# MintyCharger_Rev_A.net
KiCad netlist of a schematic drawn in EAGLE
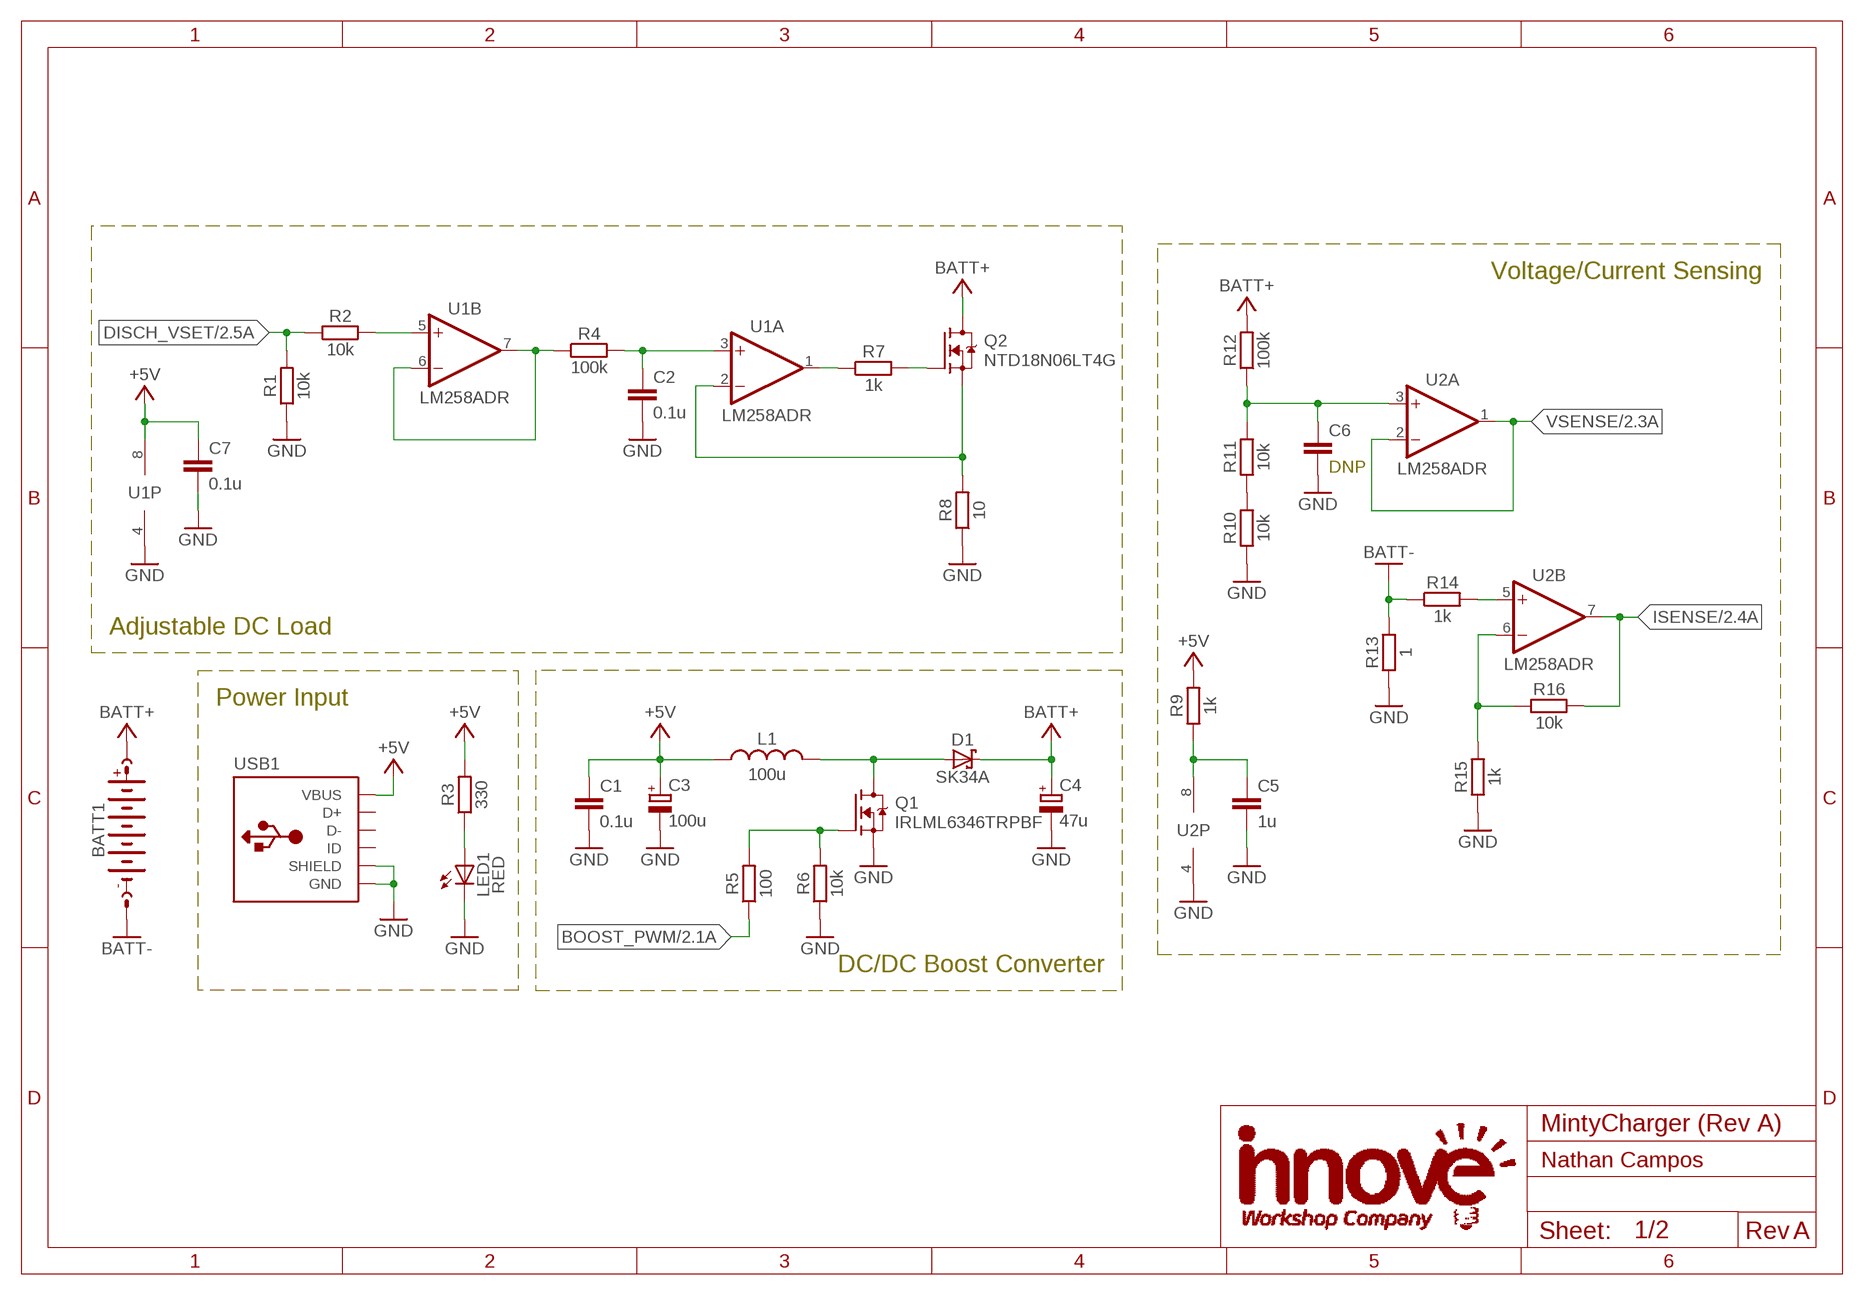
[diagram p0: schematic, sheet 1]
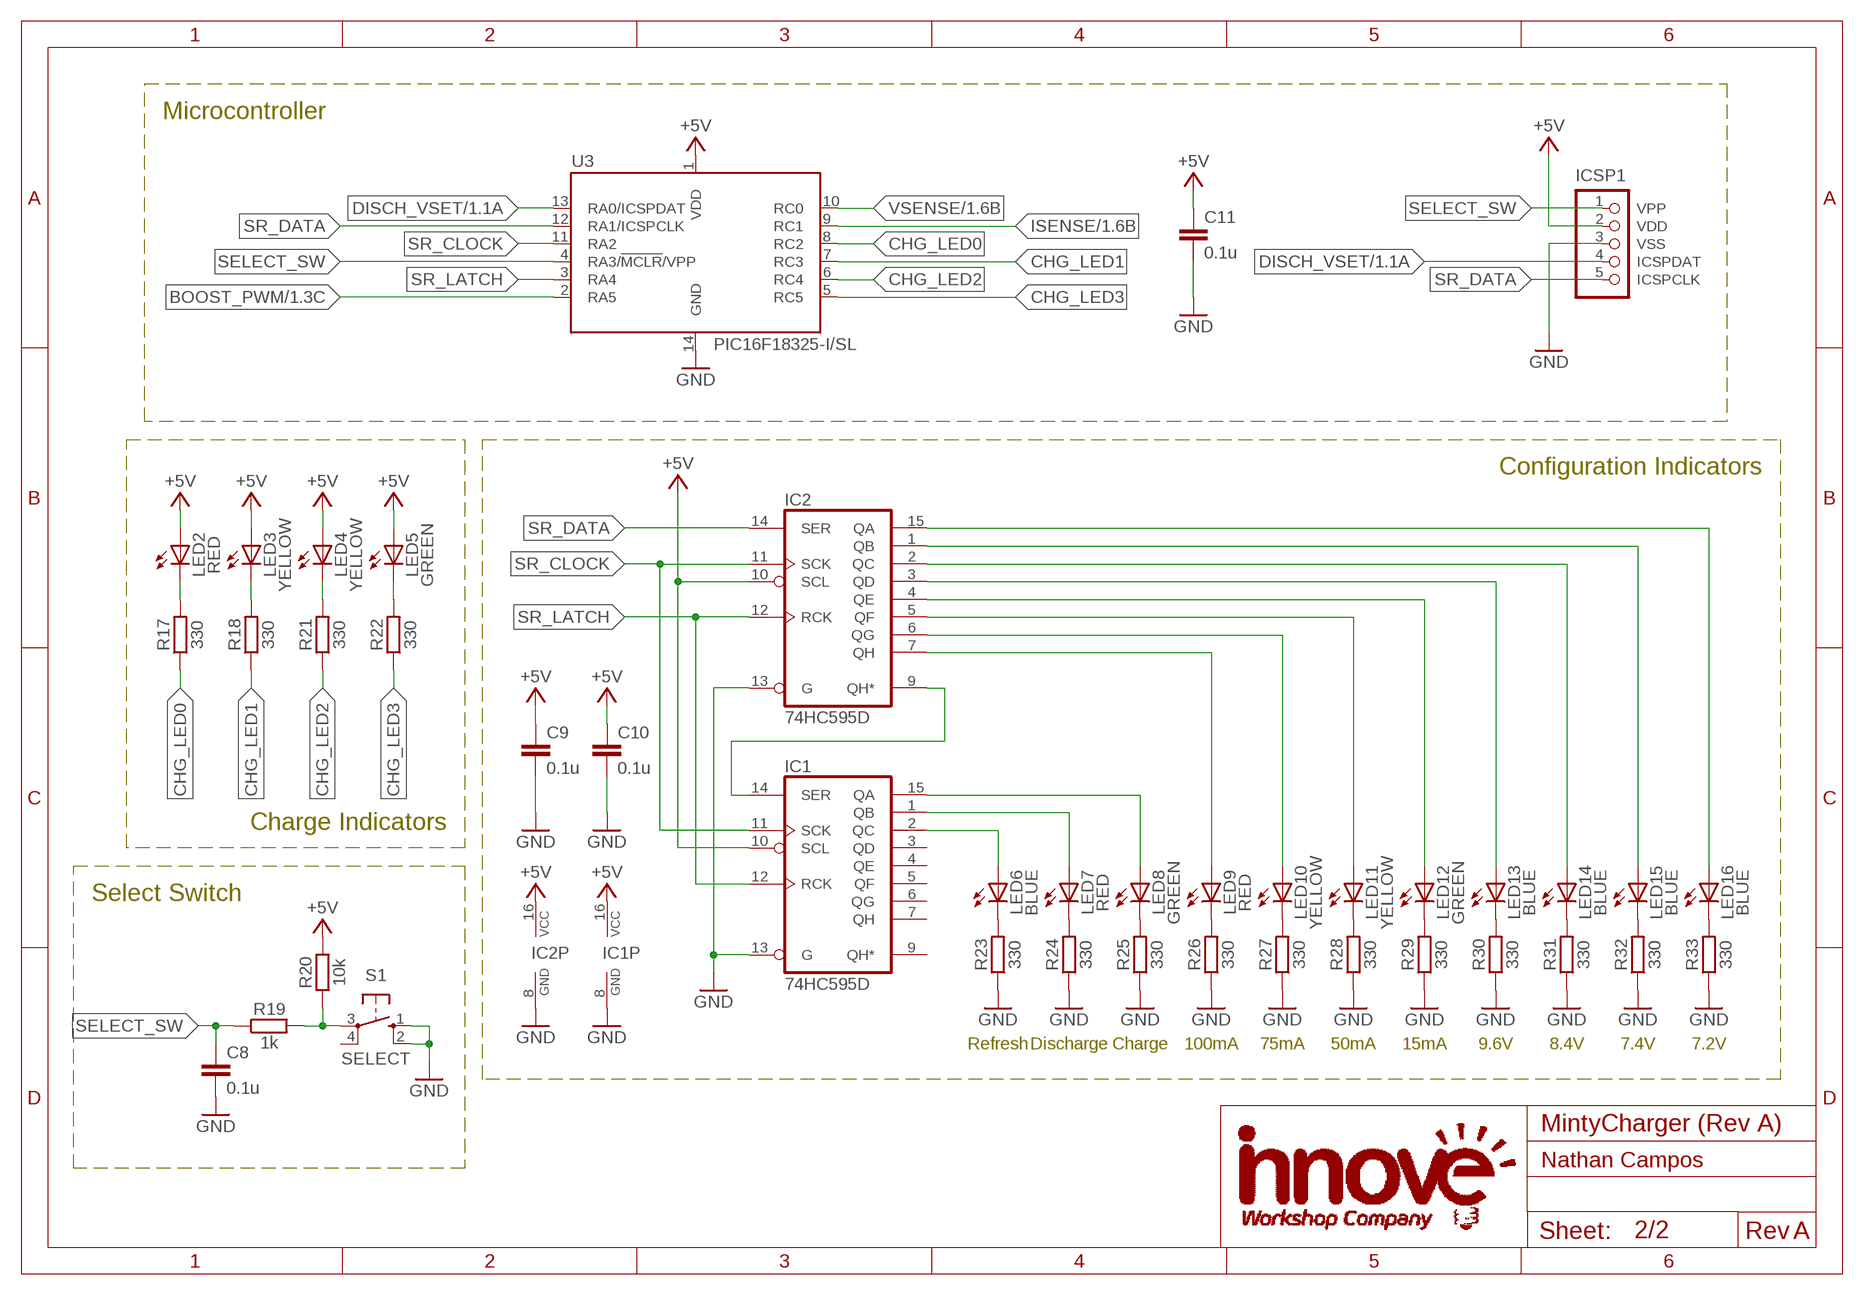
[diagram p1: schematic, sheet 2]

(export (version "E")
  (design (tool "Eeschema 10.0.6"))
  (components
    (comp (ref "C8")
      (value "0.1u")
      (footprint "eagle-import:C0805")
      (libsource (lib "eagle-import") (part "C0805"))
    )
    (comp (ref "C9")
      (value "0.1u")
      (footprint "eagle-import:C0805")
      (libsource (lib "eagle-import") (part "C0805"))
    )
    (comp (ref "C10")
      (value "0.1u")
      (footprint "eagle-import:C0805")
      (libsource (lib "eagle-import") (part "C0805"))
    )
    (comp (ref "C11")
      (value "0.1u")
      (footprint "eagle-import:C0805")
      (libsource (lib "eagle-import") (part "C0805"))
    )
    (comp (ref "IC1")
      (value "74HC595D")
      (footprint "eagle-import:SO16")
      (libsource (lib "eagle-import") (part "74595DHC"))
    )
    (comp (ref "IC2")
      (value "74HC595D")
      (footprint "eagle-import:SO16")
      (libsource (lib "eagle-import") (part "74595DHC"))
    )
    (comp (ref "ICSP1")
      (value "PIC-ICSPJST-XH")
      (footprint "eagle-import:B5B-XH-A")
      (libsource (lib "eagle-import") (part "PIC-ICSPJST-XH"))
    )
    (comp (ref "LED2")
      (value "RED")
      (footprint "eagle-import:CHIP-LED0805")
      (libsource (lib "eagle-import") (part "LEDCHIP-LED0805"))
    )
    (comp (ref "LED3")
      (value "YELLOW")
      (footprint "eagle-import:CHIP-LED0805")
      (libsource (lib "eagle-import") (part "LEDCHIP-LED0805"))
    )
    (comp (ref "LED4")
      (value "YELLOW")
      (footprint "eagle-import:CHIP-LED0805")
      (libsource (lib "eagle-import") (part "LEDCHIP-LED0805"))
    )
    (comp (ref "LED5")
      (value "GREEN")
      (footprint "eagle-import:CHIP-LED0805")
      (libsource (lib "eagle-import") (part "LEDCHIP-LED0805"))
    )
    (comp (ref "LED6")
      (value "BLUE")
      (footprint "eagle-import:CHIP-LED0805")
      (libsource (lib "eagle-import") (part "LEDCHIP-LED0805"))
    )
    (comp (ref "LED7")
      (value "RED")
      (footprint "eagle-import:CHIP-LED0805")
      (libsource (lib "eagle-import") (part "LEDCHIP-LED0805"))
    )
    (comp (ref "LED8")
      (value "GREEN")
      (footprint "eagle-import:CHIP-LED0805")
      (libsource (lib "eagle-import") (part "LEDCHIP-LED0805"))
    )
    (comp (ref "LED9")
      (value "RED")
      (footprint "eagle-import:CHIP-LED0805")
      (libsource (lib "eagle-import") (part "LEDCHIP-LED0805"))
    )
    (comp (ref "LED10")
      (value "YELLOW")
      (footprint "eagle-import:CHIP-LED0805")
      (libsource (lib "eagle-import") (part "LEDCHIP-LED0805"))
    )
    (comp (ref "LED11")
      (value "YELLOW")
      (footprint "eagle-import:CHIP-LED0805")
      (libsource (lib "eagle-import") (part "LEDCHIP-LED0805"))
    )
    (comp (ref "LED12")
      (value "GREEN")
      (footprint "eagle-import:CHIP-LED0805")
      (libsource (lib "eagle-import") (part "LEDCHIP-LED0805"))
    )
    (comp (ref "LED13")
      (value "BLUE")
      (footprint "eagle-import:CHIP-LED0805")
      (libsource (lib "eagle-import") (part "LEDCHIP-LED0805"))
    )
    (comp (ref "LED14")
      (value "BLUE")
      (footprint "eagle-import:CHIP-LED0805")
      (libsource (lib "eagle-import") (part "LEDCHIP-LED0805"))
    )
    (comp (ref "LED15")
      (value "BLUE")
      (footprint "eagle-import:CHIP-LED0805")
      (libsource (lib "eagle-import") (part "LEDCHIP-LED0805"))
    )
    (comp (ref "LED16")
      (value "BLUE")
      (footprint "eagle-import:CHIP-LED0805")
      (libsource (lib "eagle-import") (part "LEDCHIP-LED0805"))
    )
    (comp (ref "R17")
      (value "330")
      (footprint "eagle-import:R0805")
      (libsource (lib "eagle-import") (part "R0805"))
    )
    (comp (ref "R18")
      (value "330")
      (footprint "eagle-import:R0805")
      (libsource (lib "eagle-import") (part "R0805"))
    )
    (comp (ref "R19")
      (value "1k")
      (footprint "eagle-import:R0805")
      (libsource (lib "eagle-import") (part "R0805"))
    )
    (comp (ref "R20")
      (value "10k")
      (footprint "eagle-import:R0805")
      (libsource (lib "eagle-import") (part "R0805"))
    )
    (comp (ref "R21")
      (value "330")
      (footprint "eagle-import:R0805")
      (libsource (lib "eagle-import") (part "R0805"))
    )
    (comp (ref "R22")
      (value "330")
      (footprint "eagle-import:R0805")
      (libsource (lib "eagle-import") (part "R0805"))
    )
    (comp (ref "R23")
      (value "330")
      (footprint "eagle-import:R0805")
      (libsource (lib "eagle-import") (part "R0805"))
    )
    (comp (ref "R24")
      (value "330")
      (footprint "eagle-import:R0805")
      (libsource (lib "eagle-import") (part "R0805"))
    )
    (comp (ref "R25")
      (value "330")
      (footprint "eagle-import:R0805")
      (libsource (lib "eagle-import") (part "R0805"))
    )
    (comp (ref "R26")
      (value "330")
      (footprint "eagle-import:R0805")
      (libsource (lib "eagle-import") (part "R0805"))
    )
    (comp (ref "R27")
      (value "330")
      (footprint "eagle-import:R0805")
      (libsource (lib "eagle-import") (part "R0805"))
    )
    (comp (ref "R28")
      (value "330")
      (footprint "eagle-import:R0805")
      (libsource (lib "eagle-import") (part "R0805"))
    )
    (comp (ref "R29")
      (value "330")
      (footprint "eagle-import:R0805")
      (libsource (lib "eagle-import") (part "R0805"))
    )
    (comp (ref "R30")
      (value "330")
      (footprint "eagle-import:R0805")
      (libsource (lib "eagle-import") (part "R0805"))
    )
    (comp (ref "R31")
      (value "330")
      (footprint "eagle-import:R0805")
      (libsource (lib "eagle-import") (part "R0805"))
    )
    (comp (ref "R32")
      (value "330")
      (footprint "eagle-import:R0805")
      (libsource (lib "eagle-import") (part "R0805"))
    )
    (comp (ref "R33")
      (value "330")
      (footprint "eagle-import:R0805")
      (libsource (lib "eagle-import") (part "R0805"))
    )
    (comp (ref "S1")
      (value "SELECT")
      (footprint "eagle-import:PTS645-SMT")
      (libsource (lib "eagle-import") (part "TACT-4PIN-SMT"))
    )
    (comp (ref "U3")
      (value "PIC16F18325-I/SL")
      (footprint "eagle-import:SO14")
      (libsource (lib "eagle-import") (part "PIC16F18325-I/SL"))
    )
    (comp (ref "BATT1")
      (value "KEYSTONE-590-9V")
      (footprint "eagle-import:KEYSTONE-590-9V")
      (libsource (lib "eagle-import") (part "KEYSTONE-590-9V"))
    )
    (comp (ref "C1")
      (value "0.1u")
      (footprint "eagle-import:C0805")
      (libsource (lib "eagle-import") (part "C0805"))
    )
    (comp (ref "C2")
      (value "0.1u")
      (footprint "eagle-import:C0805")
      (libsource (lib "eagle-import") (part "C0805"))
    )
    (comp (ref "C3")
      (value "100u")
      (footprint "eagle-import:PANASONIC_D")
      (libsource (lib "eagle-import") (part "CPOL-MCVVT016M101EA1L"))
    )
    (comp (ref "C4")
      (value "47u")
      (footprint "eagle-import:PANASONIC_C")
      (libsource (lib "eagle-import") (part "CPOL-MCVVT016M470DA1L"))
    )
    (comp (ref "C5")
      (value "1u")
      (footprint "eagle-import:C0805")
      (libsource (lib "eagle-import") (part "C0805"))
    )
    (comp (ref "C6")
      (value "C0805")
      (footprint "eagle-import:C0805")
      (libsource (lib "eagle-import") (part "C0805"))
    )
    (comp (ref "C7")
      (value "0.1u")
      (footprint "eagle-import:C0805")
      (libsource (lib "eagle-import") (part "C0805"))
    )
    (comp (ref "D1")
      (value "SK34A")
      (footprint "eagle-import:SMA")
      (libsource (lib "eagle-import") (part "SK34A"))
    )
    (comp (ref "L1")
      (value "100u")
      (footprint "eagle-import:ELLCTP")
      (libsource (lib "eagle-import") (part "L-ELLCTP"))
    )
    (comp (ref "LED1")
      (value "RED")
      (footprint "eagle-import:CHIP-LED0805")
      (libsource (lib "eagle-import") (part "LEDCHIP-LED0805"))
    )
    (comp (ref "Q1")
      (value "IRLML6346TRPBF")
      (footprint "eagle-import:SOT23")
      (libsource (lib "eagle-import") (part "IRLML6346TRPBF"))
    )
    (comp (ref "Q2")
      (value "NTD18N06LT4G")
      (footprint "eagle-import:TO252")
      (libsource (lib "eagle-import") (part "NTD18N06LT4G"))
    )
    (comp (ref "R1")
      (value "10k")
      (footprint "eagle-import:R0805")
      (libsource (lib "eagle-import") (part "R0805"))
    )
    (comp (ref "R2")
      (value "10k")
      (footprint "eagle-import:R0805")
      (libsource (lib "eagle-import") (part "R0805"))
    )
    (comp (ref "R3")
      (value "330")
      (footprint "eagle-import:R0805")
      (libsource (lib "eagle-import") (part "R0805"))
    )
    (comp (ref "R4")
      (value "100k")
      (footprint "eagle-import:R0805")
      (libsource (lib "eagle-import") (part "R0805"))
    )
    (comp (ref "R5")
      (value "100")
      (footprint "eagle-import:R0805")
      (libsource (lib "eagle-import") (part "R0805"))
    )
    (comp (ref "R6")
      (value "10k")
      (footprint "eagle-import:R0805")
      (libsource (lib "eagle-import") (part "R0805"))
    )
    (comp (ref "R7")
      (value "1k")
      (footprint "eagle-import:R0805")
      (libsource (lib "eagle-import") (part "R0805"))
    )
    (comp (ref "R8")
      (value "10")
      (footprint "eagle-import:R1206")
      (libsource (lib "eagle-import") (part "R1206"))
    )
    (comp (ref "R9")
      (value "1k")
      (footprint "eagle-import:R0805")
      (libsource (lib "eagle-import") (part "R0805"))
    )
    (comp (ref "R10")
      (value "10k")
      (footprint "eagle-import:R0805")
      (libsource (lib "eagle-import") (part "R0805"))
    )
    (comp (ref "R11")
      (value "10k")
      (footprint "eagle-import:R0805")
      (libsource (lib "eagle-import") (part "R0805"))
    )
    (comp (ref "R12")
      (value "100k")
      (footprint "eagle-import:R0805")
      (libsource (lib "eagle-import") (part "R0805"))
    )
    (comp (ref "R13")
      (value "1")
      (footprint "eagle-import:R1206")
      (libsource (lib "eagle-import") (part "R1206"))
    )
    (comp (ref "R14")
      (value "1k")
      (footprint "eagle-import:R0805")
      (libsource (lib "eagle-import") (part "R0805"))
    )
    (comp (ref "R15")
      (value "1k")
      (footprint "eagle-import:R0805")
      (libsource (lib "eagle-import") (part "R0805"))
    )
    (comp (ref "R16")
      (value "10k")
      (footprint "eagle-import:R0805")
      (libsource (lib "eagle-import") (part "R0805"))
    )
    (comp (ref "U1")
      (value "LM258ADR")
      (footprint "eagle-import:SO08")
      (libsource (lib "eagle-import") (part "LM258ADR"))
    )
    (comp (ref "U2")
      (value "LM258ADR")
      (footprint "eagle-import:SO08")
      (libsource (lib "eagle-import") (part "LM258ADR"))
    )
    (comp (ref "USB1")
      (value "USB-MICRO-10118194-0001LF")
      (footprint "eagle-import:AMPHENOL_10118194-0001LF")
      (libsource (lib "eagle-import") (part "USB-MICRO-10118194-0001LF"))
    )
  )
  (nets
    (net (code "1") (name "+5V") (class "Default")
      (node (ref "C1") (pin "1") (pinfunction "1_1") (pintype "passive"))
      (node (ref "C10") (pin "1") (pinfunction "1_1") (pintype "passive"))
      (node (ref "C11") (pin "1") (pinfunction "1_1") (pintype "passive"))
      (node (ref "C3") (pin "+") (pinfunction "+_+") (pintype "passive"))
      (node (ref "C7") (pin "1") (pinfunction "1_1") (pintype "passive"))
      (node (ref "C9") (pin "1") (pinfunction "1_1") (pintype "passive"))
      (node (ref "IC1") (pin "10") (pinfunction "SCL_10") (pintype "input"))
      (node (ref "IC1") (pin "16") (pinfunction "VCC_16") (pintype "power_in"))
      (node (ref "IC2") (pin "10") (pinfunction "SCL_10") (pintype "input"))
      (node (ref "IC2") (pin "16") (pinfunction "VCC_16") (pintype "power_in"))
      (node (ref "ICSP1") (pin "2") (pinfunction "VDD_2") (pintype "passive"))
      (node (ref "L1") (pin "P$1") (pinfunction "1_P$1") (pintype "passive"))
      (node (ref "LED2") (pin "A") (pinfunction "A_A") (pintype "passive"))
      (node (ref "LED3") (pin "A") (pinfunction "A_A") (pintype "passive"))
      (node (ref "LED4") (pin "A") (pinfunction "A_A") (pintype "passive"))
      (node (ref "LED5") (pin "A") (pinfunction "A_A") (pintype "passive"))
      (node (ref "R20") (pin "2") (pinfunction "2_2") (pintype "passive"))
      (node (ref "R3") (pin "2") (pinfunction "2_2") (pintype "passive"))
      (node (ref "R9") (pin "2") (pinfunction "2_2") (pintype "passive"))
      (node (ref "U1") (pin "8") (pinfunction "V+_8") (pintype "power_in"))
      (node (ref "U3") (pin "1") (pinfunction "VDD_1") (pintype "power_in"))
      (node (ref "USB1") (pin "VCC") (pinfunction "VBUS_VCC") (pintype "power_in"))
    )
    (net (code "2") (name "BATT+") (class "Default")
      (node (ref "BATT1") (pin "P$+1") (pinfunction "+_P$+1") (pintype "power_in"))
      (node (ref "BATT1") (pin "P$+2") (pinfunction "+_P$+2") (pintype "power_in"))
      (node (ref "BATT1") (pin "P$+3") (pinfunction "+_P$+3") (pintype "power_in"))
      (node (ref "C4") (pin "+") (pinfunction "+_+") (pintype "passive"))
      (node (ref "D1") (pin "C") (pinfunction "C_C") (pintype "passive"))
      (node (ref "Q2") (pin "3") (pinfunction "D_3") (pintype "passive"))
      (node (ref "R12") (pin "2") (pinfunction "2_2") (pintype "passive"))
    )
    (net (code "3") (name "BATT-") (class "Default")
      (node (ref "BATT1") (pin "P$-1") (pinfunction "-_P$-1") (pintype "power_in"))
      (node (ref "BATT1") (pin "P$-2") (pinfunction "-_P$-2") (pintype "power_in"))
      (node (ref "BATT1") (pin "P$-3") (pinfunction "-_P$-3") (pintype "power_in"))
      (node (ref "R13") (pin "2") (pinfunction "2_2") (pintype "passive"))
      (node (ref "R14") (pin "1") (pinfunction "1_1") (pintype "passive"))
    )
    (net (code "4") (name "BOOST_PWM") (class "Default")
      (node (ref "R5") (pin "1") (pinfunction "1_1") (pintype "passive"))
      (node (ref "U3") (pin "2") (pinfunction "RA5_2") (pintype "bidirectional"))
    )
    (net (code "5") (name "CHG_LED0") (class "Default")
      (node (ref "R17") (pin "1") (pinfunction "1_1") (pintype "passive"))
      (node (ref "U3") (pin "8") (pinfunction "RC2_8") (pintype "bidirectional"))
    )
    (net (code "6") (name "CHG_LED1") (class "Default")
      (node (ref "R18") (pin "1") (pinfunction "1_1") (pintype "passive"))
      (node (ref "U3") (pin "7") (pinfunction "RC3_7") (pintype "bidirectional"))
    )
    (net (code "7") (name "CHG_LED2") (class "Default")
      (node (ref "R21") (pin "1") (pinfunction "1_1") (pintype "passive"))
      (node (ref "U3") (pin "6") (pinfunction "RC4_6") (pintype "bidirectional"))
    )
    (net (code "8") (name "CHG_LED3") (class "Default")
      (node (ref "R22") (pin "1") (pinfunction "1_1") (pintype "passive"))
      (node (ref "U3") (pin "5") (pinfunction "RC5_5") (pintype "bidirectional"))
    )
    (net (code "9") (name "DISCH_VSET") (class "Default")
      (node (ref "ICSP1") (pin "4") (pinfunction "ICSPDAT_4") (pintype "passive"))
      (node (ref "R1") (pin "2") (pinfunction "2_2") (pintype "passive"))
      (node (ref "R2") (pin "1") (pinfunction "1_1") (pintype "passive"))
      (node (ref "U3") (pin "13") (pinfunction "RA0/ICSPDAT_13") (pintype "bidirectional"))
    )
    (net (code "10") (name "GND") (class "Default")
      (node (ref "C1") (pin "2") (pinfunction "2_2") (pintype "passive"))
      (node (ref "C10") (pin "2") (pinfunction "2_2") (pintype "passive"))
      (node (ref "C11") (pin "2") (pinfunction "2_2") (pintype "passive"))
      (node (ref "C2") (pin "2") (pinfunction "2_2") (pintype "passive"))
      (node (ref "C3") (pin "-") (pinfunction "-_-") (pintype "passive"))
      (node (ref "C4") (pin "-") (pinfunction "-_-") (pintype "passive"))
      (node (ref "C5") (pin "2") (pinfunction "2_2") (pintype "passive"))
      (node (ref "C6") (pin "2") (pinfunction "2_2") (pintype "passive"))
      (node (ref "C7") (pin "2") (pinfunction "2_2") (pintype "passive"))
      (node (ref "C8") (pin "2") (pinfunction "2_2") (pintype "passive"))
      (node (ref "C9") (pin "2") (pinfunction "2_2") (pintype "passive"))
      (node (ref "IC1") (pin "13") (pinfunction "G_13") (pintype "input"))
      (node (ref "IC1") (pin "8") (pinfunction "GND_8") (pintype "power_in"))
      (node (ref "IC2") (pin "13") (pinfunction "G_13") (pintype "input"))
      (node (ref "IC2") (pin "8") (pinfunction "GND_8") (pintype "power_in"))
      (node (ref "ICSP1") (pin "3") (pinfunction "VSS_3") (pintype "passive"))
      (node (ref "LED1") (pin "C") (pinfunction "C_C") (pintype "passive"))
      (node (ref "Q1") (pin "2") (pinfunction "S_2") (pintype "passive"))
      (node (ref "R1") (pin "1") (pinfunction "1_1") (pintype "passive"))
      (node (ref "R10") (pin "1") (pinfunction "1_1") (pintype "passive"))
      (node (ref "R13") (pin "1") (pinfunction "1_1") (pintype "passive"))
      (node (ref "R15") (pin "1") (pinfunction "1_1") (pintype "passive"))
      (node (ref "R23") (pin "1") (pinfunction "1_1") (pintype "passive"))
      (node (ref "R24") (pin "1") (pinfunction "1_1") (pintype "passive"))
      (node (ref "R25") (pin "1") (pinfunction "1_1") (pintype "passive"))
      (node (ref "R26") (pin "1") (pinfunction "1_1") (pintype "passive"))
      (node (ref "R27") (pin "1") (pinfunction "1_1") (pintype "passive"))
      (node (ref "R28") (pin "1") (pinfunction "1_1") (pintype "passive"))
      (node (ref "R29") (pin "1") (pinfunction "1_1") (pintype "passive"))
      (node (ref "R30") (pin "1") (pinfunction "1_1") (pintype "passive"))
      (node (ref "R31") (pin "1") (pinfunction "1_1") (pintype "passive"))
      (node (ref "R32") (pin "1") (pinfunction "1_1") (pintype "passive"))
      (node (ref "R33") (pin "1") (pinfunction "1_1") (pintype "passive"))
      (node (ref "R6") (pin "1") (pinfunction "1_1") (pintype "passive"))
      (node (ref "R8") (pin "1") (pinfunction "1_1") (pintype "passive"))
      (node (ref "S1") (pin "1") (pinfunction "S_1") (pintype "passive"))
      (node (ref "S1") (pin "2") (pinfunction "S1_2") (pintype "passive"))
      (node (ref "U1") (pin "4") (pinfunction "V-_4") (pintype "power_in"))
      (node (ref "U2") (pin "4") (pinfunction "V-_4") (pintype "power_in"))
      (node (ref "U3") (pin "14") (pinfunction "GND_14") (pintype "power_in"))
      (node (ref "USB1") (pin "GND") (pinfunction "GND_GND") (pintype "power_in"))
      (node (ref "USB1") (pin "S1") (pinfunction "SHIELD_S1") (pintype "power_in"))
      (node (ref "USB1") (pin "S2") (pinfunction "SHIELD_S2") (pintype "power_in"))
      (node (ref "USB1") (pin "S3") (pinfunction "SHIELD_S3") (pintype "power_in"))
      (node (ref "USB1") (pin "S4") (pinfunction "SHIELD_S4") (pintype "power_in"))
      (node (ref "USB1") (pin "S5") (pinfunction "SHIELD_S5") (pintype "power_in"))
      (node (ref "USB1") (pin "S6") (pinfunction "SHIELD_S6") (pintype "power_in"))
      (node (ref "USB1") (pin "S7") (pinfunction "SHIELD_S7") (pintype "power_in"))
      (node (ref "USB1") (pin "S8") (pinfunction "SHIELD_S8") (pintype "power_in"))
    )
    (net (code "11") (name "ISENSE") (class "Default")
      (node (ref "R16") (pin "2") (pinfunction "2_2") (pintype "passive"))
      (node (ref "U2") (pin "7") (pinfunction "OUT_7") (pintype "output"))
      (node (ref "U3") (pin "9") (pinfunction "RC1_9") (pintype "bidirectional"))
    )
    (net (code "12") (name "Net-(IC1A-QA)") (class "Default")
      (node (ref "IC1") (pin "15") (pinfunction "QA_15") (pintype "tri_state"))
      (node (ref "LED8") (pin "A") (pinfunction "A_A") (pintype "passive"))
    )
    (net (code "13") (name "Net-(IC1A-QB)") (class "Default")
      (node (ref "IC1") (pin "1") (pinfunction "QB_1") (pintype "tri_state"))
      (node (ref "LED7") (pin "A") (pinfunction "A_A") (pintype "passive"))
    )
    (net (code "14") (name "Net-(IC1A-QC)") (class "Default")
      (node (ref "IC1") (pin "2") (pinfunction "QC_2") (pintype "tri_state"))
      (node (ref "LED6") (pin "A") (pinfunction "A_A") (pintype "passive"))
    )
    (net (code "15") (name "Net-(IC1A-SER)") (class "Default")
      (node (ref "IC1") (pin "14") (pinfunction "SER_14") (pintype "input"))
      (node (ref "IC2") (pin "9") (pinfunction "QH*_9") (pintype "tri_state"))
    )
    (net (code "16") (name "Net-(IC2A-QA)") (class "Default")
      (node (ref "IC2") (pin "15") (pinfunction "QA_15") (pintype "tri_state"))
      (node (ref "LED16") (pin "A") (pinfunction "A_A") (pintype "passive"))
    )
    (net (code "17") (name "Net-(IC2A-QB)") (class "Default")
      (node (ref "IC2") (pin "1") (pinfunction "QB_1") (pintype "tri_state"))
      (node (ref "LED15") (pin "A") (pinfunction "A_A") (pintype "passive"))
    )
    (net (code "18") (name "Net-(IC2A-QC)") (class "Default")
      (node (ref "IC2") (pin "2") (pinfunction "QC_2") (pintype "tri_state"))
      (node (ref "LED14") (pin "A") (pinfunction "A_A") (pintype "passive"))
    )
    (net (code "19") (name "Net-(IC2A-QD)") (class "Default")
      (node (ref "IC2") (pin "3") (pinfunction "QD_3") (pintype "tri_state"))
      (node (ref "LED13") (pin "A") (pinfunction "A_A") (pintype "passive"))
    )
    (net (code "20") (name "Net-(IC2A-QE)") (class "Default")
      (node (ref "IC2") (pin "4") (pinfunction "QE_4") (pintype "tri_state"))
      (node (ref "LED12") (pin "A") (pinfunction "A_A") (pintype "passive"))
    )
    (net (code "21") (name "Net-(IC2A-QF)") (class "Default")
      (node (ref "IC2") (pin "5") (pinfunction "QF_5") (pintype "tri_state"))
      (node (ref "LED11") (pin "A") (pinfunction "A_A") (pintype "passive"))
    )
    (net (code "22") (name "Net-(IC2A-QG)") (class "Default")
      (node (ref "IC2") (pin "6") (pinfunction "QG_6") (pintype "tri_state"))
      (node (ref "LED10") (pin "A") (pinfunction "A_A") (pintype "passive"))
    )
    (net (code "23") (name "Net-(IC2A-QH)") (class "Default")
      (node (ref "IC2") (pin "7") (pinfunction "QH_7") (pintype "tri_state"))
      (node (ref "LED9") (pin "A") (pinfunction "A_A") (pintype "passive"))
    )
    (net (code "24") (name "Net-(L1-2)") (class "Default")
      (node (ref "D1") (pin "A") (pinfunction "A_A") (pintype "passive"))
      (node (ref "L1") (pin "P$2") (pinfunction "2_P$2") (pintype "passive"))
      (node (ref "Q1") (pin "3") (pinfunction "D_3") (pintype "passive"))
    )
    (net (code "25") (name "Net-(LED1-PadA)") (class "Default")
      (node (ref "LED1") (pin "A") (pinfunction "A_A") (pintype "passive"))
      (node (ref "R3") (pin "1") (pinfunction "1_1") (pintype "passive"))
    )
    (net (code "26") (name "Net-(LED2-PadC)") (class "Default")
      (node (ref "LED2") (pin "C") (pinfunction "C_C") (pintype "passive"))
      (node (ref "R17") (pin "2") (pinfunction "2_2") (pintype "passive"))
    )
    (net (code "27") (name "Net-(LED3-PadC)") (class "Default")
      (node (ref "LED3") (pin "C") (pinfunction "C_C") (pintype "passive"))
      (node (ref "R18") (pin "2") (pinfunction "2_2") (pintype "passive"))
    )
    (net (code "28") (name "Net-(LED4-PadC)") (class "Default")
      (node (ref "LED4") (pin "C") (pinfunction "C_C") (pintype "passive"))
      (node (ref "R21") (pin "2") (pinfunction "2_2") (pintype "passive"))
    )
    (net (code "29") (name "Net-(LED5-PadC)") (class "Default")
      (node (ref "LED5") (pin "C") (pinfunction "C_C") (pintype "passive"))
      (node (ref "R22") (pin "2") (pinfunction "2_2") (pintype "passive"))
    )
    (net (code "30") (name "Net-(LED6-PadC)") (class "Default")
      (node (ref "LED6") (pin "C") (pinfunction "C_C") (pintype "passive"))
      (node (ref "R23") (pin "2") (pinfunction "2_2") (pintype "passive"))
    )
    (net (code "31") (name "Net-(LED7-PadC)") (class "Default")
      (node (ref "LED7") (pin "C") (pinfunction "C_C") (pintype "passive"))
      (node (ref "R24") (pin "2") (pinfunction "2_2") (pintype "passive"))
    )
    (net (code "32") (name "Net-(LED8-PadC)") (class "Default")
      (node (ref "LED8") (pin "C") (pinfunction "C_C") (pintype "passive"))
      (node (ref "R25") (pin "2") (pinfunction "2_2") (pintype "passive"))
    )
    (net (code "33") (name "Net-(LED9-PadC)") (class "Default")
      (node (ref "LED9") (pin "C") (pinfunction "C_C") (pintype "passive"))
      (node (ref "R26") (pin "2") (pinfunction "2_2") (pintype "passive"))
    )
    (net (code "34") (name "Net-(LED10-PadC)") (class "Default")
      (node (ref "LED10") (pin "C") (pinfunction "C_C") (pintype "passive"))
      (node (ref "R27") (pin "2") (pinfunction "2_2") (pintype "passive"))
    )
    (net (code "35") (name "Net-(LED11-PadC)") (class "Default")
      (node (ref "LED11") (pin "C") (pinfunction "C_C") (pintype "passive"))
      (node (ref "R28") (pin "2") (pinfunction "2_2") (pintype "passive"))
    )
    (net (code "36") (name "Net-(LED12-PadC)") (class "Default")
      (node (ref "LED12") (pin "C") (pinfunction "C_C") (pintype "passive"))
      (node (ref "R29") (pin "2") (pinfunction "2_2") (pintype "passive"))
    )
    (net (code "37") (name "Net-(LED13-PadC)") (class "Default")
      (node (ref "LED13") (pin "C") (pinfunction "C_C") (pintype "passive"))
      (node (ref "R30") (pin "2") (pinfunction "2_2") (pintype "passive"))
    )
    (net (code "38") (name "Net-(LED14-PadC)") (class "Default")
      (node (ref "LED14") (pin "C") (pinfunction "C_C") (pintype "passive"))
      (node (ref "R31") (pin "2") (pinfunction "2_2") (pintype "passive"))
    )
    (net (code "39") (name "Net-(LED15-PadC)") (class "Default")
      (node (ref "LED15") (pin "C") (pinfunction "C_C") (pintype "passive"))
      (node (ref "R32") (pin "2") (pinfunction "2_2") (pintype "passive"))
    )
    (net (code "40") (name "Net-(LED16-PadC)") (class "Default")
      (node (ref "LED16") (pin "C") (pinfunction "C_C") (pintype "passive"))
      (node (ref "R33") (pin "2") (pinfunction "2_2") (pintype "passive"))
    )
    (net (code "41") (name "Net-(Q1-G)") (class "Default")
      (node (ref "Q1") (pin "1") (pinfunction "G_1") (pintype "passive"))
      (node (ref "R5") (pin "2") (pinfunction "2_2") (pintype "passive"))
      (node (ref "R6") (pin "2") (pinfunction "2_2") (pintype "passive"))
    )
    (net (code "42") (name "Net-(Q2-G)") (class "Default")
      (node (ref "Q2") (pin "1") (pinfunction "G_1") (pintype "passive"))
      (node (ref "R7") (pin "2") (pinfunction "2_2") (pintype "passive"))
    )
    (net (code "43") (name "Net-(Q2-S)") (class "Default")
      (node (ref "Q2") (pin "2") (pinfunction "S_2") (pintype "passive"))
      (node (ref "R8") (pin "2") (pinfunction "2_2") (pintype "passive"))
      (node (ref "U1") (pin "2") (pinfunction "-IN_2") (pintype "input"))
    )
    (net (code "44") (name "Net-(R10-Pad2)") (class "Default")
      (node (ref "R10") (pin "2") (pinfunction "2_2") (pintype "passive"))
      (node (ref "R11") (pin "1") (pinfunction "1_1") (pintype "passive"))
    )
    (net (code "45") (name "Net-(S1-P)") (class "Default")
      (node (ref "R19") (pin "2") (pinfunction "2_2") (pintype "passive"))
      (node (ref "R20") (pin "1") (pinfunction "1_1") (pintype "passive"))
      (node (ref "S1") (pin "3") (pinfunction "P_3") (pintype "passive"))
    )
    (net (code "46") (name "Net-(U1A-+IN)") (class "Default")
      (node (ref "C2") (pin "1") (pinfunction "1_1") (pintype "passive"))
      (node (ref "R4") (pin "2") (pinfunction "2_2") (pintype "passive"))
      (node (ref "U1") (pin "3") (pinfunction "+IN_3") (pintype "input"))
    )
    (net (code "47") (name "Net-(U1A-OUT)") (class "Default")
      (node (ref "R7") (pin "1") (pinfunction "1_1") (pintype "passive"))
      (node (ref "U1") (pin "1") (pinfunction "OUT_1") (pintype "output"))
    )
    (net (code "48") (name "Net-(U1B-+IN)") (class "Default")
      (node (ref "R2") (pin "2") (pinfunction "2_2") (pintype "passive"))
      (node (ref "U1") (pin "5") (pinfunction "+IN_5") (pintype "input"))
    )
    (net (code "49") (name "Net-(U1B--IN)") (class "Default")
      (node (ref "R4") (pin "1") (pinfunction "1_1") (pintype "passive"))
      (node (ref "U1") (pin "6") (pinfunction "-IN_6") (pintype "input"))
      (node (ref "U1") (pin "7") (pinfunction "OUT_7") (pintype "output"))
    )
    (net (code "50") (name "Net-(U2A-+IN)") (class "Default")
      (node (ref "C6") (pin "1") (pinfunction "1_1") (pintype "passive"))
      (node (ref "R11") (pin "2") (pinfunction "2_2") (pintype "passive"))
      (node (ref "R12") (pin "1") (pinfunction "1_1") (pintype "passive"))
      (node (ref "U2") (pin "3") (pinfunction "+IN_3") (pintype "input"))
    )
    (net (code "51") (name "Net-(U2B-+IN)") (class "Default")
      (node (ref "R14") (pin "2") (pinfunction "2_2") (pintype "passive"))
      (node (ref "U2") (pin "5") (pinfunction "+IN_5") (pintype "input"))
    )
    (net (code "52") (name "Net-(U2B--IN)") (class "Default")
      (node (ref "R15") (pin "2") (pinfunction "2_2") (pintype "passive"))
      (node (ref "R16") (pin "1") (pinfunction "1_1") (pintype "passive"))
      (node (ref "U2") (pin "6") (pinfunction "-IN_6") (pintype "input"))
    )
    (net (code "53") (name "Net-(U2C-V+)") (class "Default")
      (node (ref "C5") (pin "1") (pinfunction "1_1") (pintype "passive"))
      (node (ref "R9") (pin "1") (pinfunction "1_1") (pintype "passive"))
      (node (ref "U2") (pin "8") (pinfunction "V+_8") (pintype "power_in"))
    )
    (net (code "54") (name "SELECT_SW") (class "Default")
      (node (ref "C8") (pin "1") (pinfunction "1_1") (pintype "passive"))
      (node (ref "ICSP1") (pin "1") (pinfunction "VPP_1") (pintype "passive"))
      (node (ref "R19") (pin "1") (pinfunction "1_1") (pintype "passive"))
      (node (ref "U3") (pin "4") (pinfunction "RA3/~{MCLR}/VPP_4") (pintype "input"))
    )
    (net (code "55") (name "SR_CLOCK") (class "Default")
      (node (ref "IC1") (pin "11") (pinfunction "SCK_11") (pintype "input"))
      (node (ref "IC2") (pin "11") (pinfunction "SCK_11") (pintype "input"))
      (node (ref "U3") (pin "11") (pinfunction "RA2_11") (pintype "bidirectional"))
    )
    (net (code "56") (name "SR_DATA") (class "Default")
      (node (ref "IC2") (pin "14") (pinfunction "SER_14") (pintype "input"))
      (node (ref "ICSP1") (pin "5") (pinfunction "ICSPCLK_5") (pintype "passive"))
      (node (ref "U3") (pin "12") (pinfunction "RA1/ICSPCLK_12") (pintype "bidirectional"))
    )
    (net (code "57") (name "SR_LATCH") (class "Default")
      (node (ref "IC1") (pin "12") (pinfunction "RCK_12") (pintype "input"))
      (node (ref "IC2") (pin "12") (pinfunction "RCK_12") (pintype "input"))
      (node (ref "U3") (pin "3") (pinfunction "RA4_3") (pintype "bidirectional"))
    )
    (net (code "58") (name "VSENSE") (class "Default")
      (node (ref "U2") (pin "1") (pinfunction "OUT_1") (pintype "output"))
      (node (ref "U2") (pin "2") (pinfunction "-IN_2") (pintype "input"))
      (node (ref "U3") (pin "10") (pinfunction "RC0_10") (pintype "bidirectional"))
    )
    (net (code "59") (name "unconnected-(IC1A-QD-Pad3)") (class "Default")
      (node (ref "IC1") (pin "3") (pinfunction "QD_3") (pintype "tri_state"))
    )
    (net (code "60") (name "unconnected-(IC1A-QE-Pad4)") (class "Default")
      (node (ref "IC1") (pin "4") (pinfunction "QE_4") (pintype "tri_state"))
    )
    (net (code "61") (name "unconnected-(IC1A-QF-Pad5)") (class "Default")
      (node (ref "IC1") (pin "5") (pinfunction "QF_5") (pintype "tri_state"))
    )
    (net (code "62") (name "unconnected-(IC1A-QG-Pad6)") (class "Default")
      (node (ref "IC1") (pin "6") (pinfunction "QG_6") (pintype "tri_state"))
    )
    (net (code "63") (name "unconnected-(IC1A-QH*-Pad9)") (class "Default")
      (node (ref "IC1") (pin "9") (pinfunction "QH*_9") (pintype "tri_state"))
    )
    (net (code "64") (name "unconnected-(IC1A-QH-Pad7)") (class "Default")
      (node (ref "IC1") (pin "7") (pinfunction "QH_7") (pintype "tri_state"))
    )
    (net (code "65") (name "unconnected-(S1-P1-Pad4)") (class "Default")
      (node (ref "S1") (pin "4") (pinfunction "P1_4") (pintype "passive"))
    )
    (net (code "66") (name "unconnected-(USB1-PadD+)") (class "Default")
      (node (ref "USB1") (pin "D+") (pinfunction "D+_D+") (pintype "bidirectional"))
    )
    (net (code "67") (name "unconnected-(USB1-PadD-)") (class "Default")
      (node (ref "USB1") (pin "D-") (pinfunction "D-_D-") (pintype "bidirectional"))
    )
    (net (code "68") (name "unconnected-(USB1-PadID)") (class "Default")
      (node (ref "USB1") (pin "ID") (pinfunction "ID_ID") (pintype "bidirectional"))
    )
  )
)
